# S_ground.net
KiCad netlist of a schematic drawn in Altium Designer
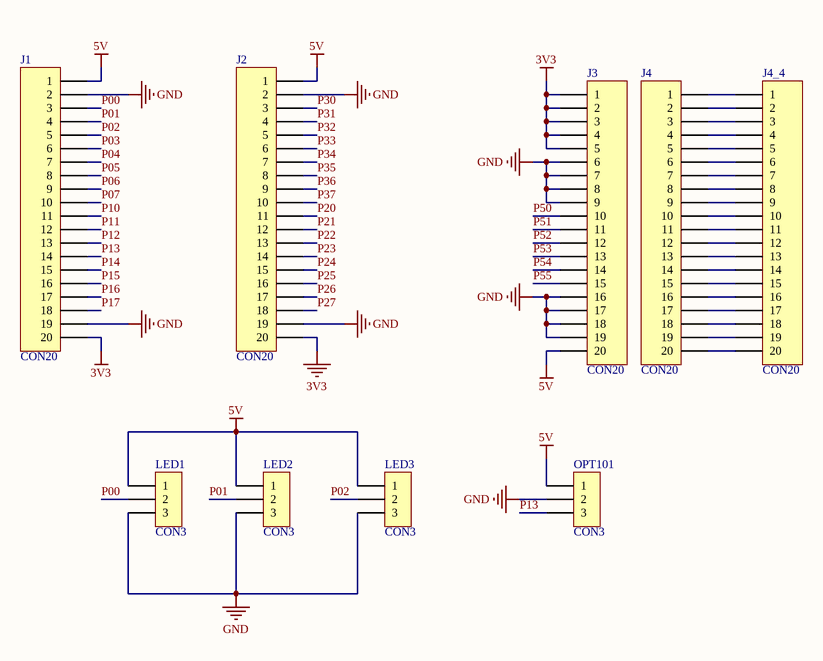
[diagram p0: S_ground.SchDoc]

(export (version "E")
  (design (tool "Eeschema 10.0.6"))
  (components
    (comp (ref "J1")
      (value "CON20")
      (footprint "sip-20")
      (description "Connector")
      (libsource (lib "") (part "CON20_1"))
    )
    (comp (ref "J2")
      (value "CON20")
      (footprint "sip-20")
      (description "Connector")
      (libsource (lib "") (part "CON20_1"))
    )
    (comp (ref "J3")
      (value "CON20")
      (footprint "sip-20")
      (description "Connector")
      (libsource (lib "科协的库") (part "CON20"))
    )
    (comp (ref "J4")
      (value "CON20")
      (footprint "sip-20")
      (description "Connector")
      (libsource (lib "") (part "CON20_1"))
    )
    (comp (ref "J4_4")
      (value "CON20")
      (footprint "sip-20")
      (description "Connector")
      (libsource (lib "科协的库") (part "CON20"))
    )
    (comp (ref "LED1")
      (value "CON3")
      (footprint "SIP-3")
      (description "Connector")
      (libsource (lib "科协的库") (part "CON3"))
    )
    (comp (ref "LED2")
      (value "CON3")
      (footprint "SIP-3")
      (description "Connector")
      (libsource (lib "科协的库") (part "CON3"))
    )
    (comp (ref "LED3")
      (value "CON3")
      (footprint "SIP-3")
      (description "Connector")
      (libsource (lib "科协的库") (part "CON3"))
    )
    (comp (ref "OPT101")
      (value "CON3")
      (footprint "SIP-3")
      (description "Connector")
      (libsource (lib "科协的库") (part "CON3"))
    )
  )
  (nets
    (net (code "1") (name "/P00") (class "Default")
      (node (ref "J1") (pin "3") (pinfunction "3_3") (pintype "passive"))
      (node (ref "LED1") (pin "2") (pinfunction "2_2") (pintype "passive"))
    )
    (net (code "2") (name "/P01") (class "Default")
      (node (ref "J1") (pin "4") (pinfunction "4_4") (pintype "passive"))
      (node (ref "LED2") (pin "2") (pinfunction "2_2") (pintype "passive"))
    )
    (net (code "3") (name "/P02") (class "Default")
      (node (ref "J1") (pin "5") (pinfunction "5_5") (pintype "passive"))
      (node (ref "LED3") (pin "2") (pinfunction "2_2") (pintype "passive"))
    )
    (net (code "4") (name "/P03") (class "Default")
      (node (ref "J1") (pin "6") (pinfunction "6_6") (pintype "passive"))
    )
    (net (code "5") (name "/P04") (class "Default")
      (node (ref "J1") (pin "7") (pinfunction "7_7") (pintype "passive"))
    )
    (net (code "6") (name "/P05") (class "Default")
      (node (ref "J1") (pin "8") (pinfunction "8_8") (pintype "passive"))
    )
    (net (code "7") (name "/P06") (class "Default")
      (node (ref "J1") (pin "9") (pinfunction "9_9") (pintype "passive"))
    )
    (net (code "8") (name "/P07") (class "Default")
      (node (ref "J1") (pin "10") (pinfunction "10_10") (pintype "passive"))
    )
    (net (code "9") (name "/P10") (class "Default")
      (node (ref "J1") (pin "11") (pinfunction "11_11") (pintype "passive"))
    )
    (net (code "10") (name "/P11") (class "Default")
      (node (ref "J1") (pin "12") (pinfunction "12_12") (pintype "passive"))
    )
    (net (code "11") (name "/P12") (class "Default")
      (node (ref "J1") (pin "13") (pinfunction "13_13") (pintype "passive"))
    )
    (net (code "12") (name "/P13") (class "Default")
      (node (ref "J1") (pin "14") (pinfunction "14_14") (pintype "passive"))
      (node (ref "OPT101") (pin "3") (pinfunction "3_3") (pintype "passive"))
    )
    (net (code "13") (name "/P14") (class "Default")
      (node (ref "J1") (pin "15") (pinfunction "15_15") (pintype "passive"))
    )
    (net (code "14") (name "/P15") (class "Default")
      (node (ref "J1") (pin "16") (pinfunction "16_16") (pintype "passive"))
    )
    (net (code "15") (name "/P16") (class "Default")
      (node (ref "J1") (pin "17") (pinfunction "17_17") (pintype "passive"))
    )
    (net (code "16") (name "/P17") (class "Default")
      (node (ref "J1") (pin "18") (pinfunction "18_18") (pintype "passive"))
    )
    (net (code "17") (name "/P20") (class "Default")
      (node (ref "J2") (pin "11") (pinfunction "11_11") (pintype "passive"))
    )
    (net (code "18") (name "/P21") (class "Default")
      (node (ref "J2") (pin "12") (pinfunction "12_12") (pintype "passive"))
    )
    (net (code "19") (name "/P22") (class "Default")
      (node (ref "J2") (pin "13") (pinfunction "13_13") (pintype "passive"))
    )
    (net (code "20") (name "/P23") (class "Default")
      (node (ref "J2") (pin "14") (pinfunction "14_14") (pintype "passive"))
    )
    (net (code "21") (name "/P24") (class "Default")
      (node (ref "J2") (pin "15") (pinfunction "15_15") (pintype "passive"))
    )
    (net (code "22") (name "/P25") (class "Default")
      (node (ref "J2") (pin "16") (pinfunction "16_16") (pintype "passive"))
    )
    (net (code "23") (name "/P26") (class "Default")
      (node (ref "J2") (pin "17") (pinfunction "17_17") (pintype "passive"))
    )
    (net (code "24") (name "/P27") (class "Default")
      (node (ref "J2") (pin "18") (pinfunction "18_18") (pintype "passive"))
    )
    (net (code "25") (name "/P30") (class "Default")
      (node (ref "J2") (pin "3") (pinfunction "3_3") (pintype "passive"))
    )
    (net (code "26") (name "/P31") (class "Default")
      (node (ref "J2") (pin "4") (pinfunction "4_4") (pintype "passive"))
    )
    (net (code "27") (name "/P32") (class "Default")
      (node (ref "J2") (pin "5") (pinfunction "5_5") (pintype "passive"))
    )
    (net (code "28") (name "/P33") (class "Default")
      (node (ref "J2") (pin "6") (pinfunction "6_6") (pintype "passive"))
    )
    (net (code "29") (name "/P34") (class "Default")
      (node (ref "J2") (pin "7") (pinfunction "7_7") (pintype "passive"))
    )
    (net (code "30") (name "/P35") (class "Default")
      (node (ref "J2") (pin "8") (pinfunction "8_8") (pintype "passive"))
    )
    (net (code "31") (name "/P36") (class "Default")
      (node (ref "J2") (pin "9") (pinfunction "9_9") (pintype "passive"))
    )
    (net (code "32") (name "/P37") (class "Default")
      (node (ref "J2") (pin "10") (pinfunction "10_10") (pintype "passive"))
    )
    (net (code "33") (name "/P50") (class "Default")
      (node (ref "J3") (pin "10") (pinfunction "10_10") (pintype "passive"))
    )
    (net (code "34") (name "/P51") (class "Default")
      (node (ref "J3") (pin "11") (pinfunction "11_11") (pintype "passive"))
    )
    (net (code "35") (name "/P52") (class "Default")
      (node (ref "J3") (pin "12") (pinfunction "12_12") (pintype "passive"))
    )
    (net (code "36") (name "/P53") (class "Default")
      (node (ref "J3") (pin "13") (pinfunction "13_13") (pintype "passive"))
    )
    (net (code "37") (name "/P54") (class "Default")
      (node (ref "J3") (pin "14") (pinfunction "14_14") (pintype "passive"))
    )
    (net (code "38") (name "/P55") (class "Default")
      (node (ref "J3") (pin "15") (pinfunction "15_15") (pintype "passive"))
    )
    (net (code "39") (name "3V3") (class "Default")
      (node (ref "J1") (pin "20") (pinfunction "20_20") (pintype "passive"))
      (node (ref "J2") (pin "20") (pinfunction "20_20") (pintype "passive"))
      (node (ref "J3") (pin "1") (pinfunction "1_1") (pintype "passive"))
      (node (ref "J3") (pin "2") (pinfunction "2_2") (pintype "passive"))
      (node (ref "J3") (pin "3") (pinfunction "3_3") (pintype "passive"))
      (node (ref "J3") (pin "4") (pinfunction "4_4") (pintype "passive"))
      (node (ref "J3") (pin "5") (pinfunction "5_5") (pintype "passive"))
    )
    (net (code "40") (name "5V") (class "Default")
      (node (ref "J1") (pin "1") (pinfunction "1_1") (pintype "passive"))
      (node (ref "J2") (pin "1") (pinfunction "1_1") (pintype "passive"))
      (node (ref "J3") (pin "20") (pinfunction "20_20") (pintype "passive"))
      (node (ref "LED1") (pin "1") (pinfunction "1_1") (pintype "passive"))
      (node (ref "LED2") (pin "1") (pinfunction "1_1") (pintype "passive"))
      (node (ref "LED3") (pin "1") (pinfunction "1_1") (pintype "passive"))
      (node (ref "OPT101") (pin "1") (pinfunction "1_1") (pintype "passive"))
    )
    (net (code "41") (name "GND") (class "Default")
      (node (ref "J1") (pin "19") (pinfunction "19_19") (pintype "passive"))
      (node (ref "J1") (pin "2") (pinfunction "2_2") (pintype "passive"))
      (node (ref "J2") (pin "19") (pinfunction "19_19") (pintype "passive"))
      (node (ref "J2") (pin "2") (pinfunction "2_2") (pintype "passive"))
      (node (ref "J3") (pin "16") (pinfunction "16_16") (pintype "passive"))
      (node (ref "J3") (pin "17") (pinfunction "17_17") (pintype "passive"))
      (node (ref "J3") (pin "18") (pinfunction "18_18") (pintype "passive"))
      (node (ref "J3") (pin "19") (pinfunction "19_19") (pintype "passive"))
      (node (ref "J3") (pin "6") (pinfunction "6_6") (pintype "passive"))
      (node (ref "J3") (pin "7") (pinfunction "7_7") (pintype "passive"))
      (node (ref "J3") (pin "8") (pinfunction "8_8") (pintype "passive"))
      (node (ref "J3") (pin "9") (pinfunction "9_9") (pintype "passive"))
      (node (ref "LED1") (pin "3") (pinfunction "3_3") (pintype "passive"))
      (node (ref "LED2") (pin "3") (pinfunction "3_3") (pintype "passive"))
      (node (ref "LED3") (pin "3") (pinfunction "3_3") (pintype "passive"))
      (node (ref "OPT101") (pin "2") (pinfunction "2_2") (pintype "passive"))
    )
    (net (code "42") (name "Net-(J4-Pad1)") (class "Default")
      (node (ref "J4") (pin "1") (pinfunction "1_1") (pintype "passive"))
      (node (ref "J4_4") (pin "1") (pinfunction "1_1") (pintype "passive"))
    )
    (net (code "43") (name "Net-(J4-Pad2)") (class "Default")
      (node (ref "J4") (pin "2") (pinfunction "2_2") (pintype "passive"))
      (node (ref "J4_4") (pin "2") (pinfunction "2_2") (pintype "passive"))
    )
    (net (code "44") (name "Net-(J4-Pad3)") (class "Default")
      (node (ref "J4") (pin "3") (pinfunction "3_3") (pintype "passive"))
      (node (ref "J4_4") (pin "3") (pinfunction "3_3") (pintype "passive"))
    )
    (net (code "45") (name "Net-(J4-Pad4)") (class "Default")
      (node (ref "J4") (pin "4") (pinfunction "4_4") (pintype "passive"))
      (node (ref "J4_4") (pin "4") (pinfunction "4_4") (pintype "passive"))
    )
    (net (code "46") (name "Net-(J4-Pad5)") (class "Default")
      (node (ref "J4") (pin "5") (pinfunction "5_5") (pintype "passive"))
      (node (ref "J4_4") (pin "5") (pinfunction "5_5") (pintype "passive"))
    )
    (net (code "47") (name "Net-(J4-Pad6)") (class "Default")
      (node (ref "J4") (pin "6") (pinfunction "6_6") (pintype "passive"))
      (node (ref "J4_4") (pin "6") (pinfunction "6_6") (pintype "passive"))
    )
    (net (code "48") (name "Net-(J4-Pad7)") (class "Default")
      (node (ref "J4") (pin "7") (pinfunction "7_7") (pintype "passive"))
      (node (ref "J4_4") (pin "7") (pinfunction "7_7") (pintype "passive"))
    )
    (net (code "49") (name "Net-(J4-Pad8)") (class "Default")
      (node (ref "J4") (pin "8") (pinfunction "8_8") (pintype "passive"))
      (node (ref "J4_4") (pin "8") (pinfunction "8_8") (pintype "passive"))
    )
    (net (code "50") (name "Net-(J4-Pad9)") (class "Default")
      (node (ref "J4") (pin "9") (pinfunction "9_9") (pintype "passive"))
      (node (ref "J4_4") (pin "9") (pinfunction "9_9") (pintype "passive"))
    )
    (net (code "51") (name "Net-(J4-Pad10)") (class "Default")
      (node (ref "J4") (pin "10") (pinfunction "10_10") (pintype "passive"))
      (node (ref "J4_4") (pin "10") (pinfunction "10_10") (pintype "passive"))
    )
    (net (code "52") (name "Net-(J4-Pad11)") (class "Default")
      (node (ref "J4") (pin "11") (pinfunction "11_11") (pintype "passive"))
      (node (ref "J4_4") (pin "11") (pinfunction "11_11") (pintype "passive"))
    )
    (net (code "53") (name "Net-(J4-Pad12)") (class "Default")
      (node (ref "J4") (pin "12") (pinfunction "12_12") (pintype "passive"))
      (node (ref "J4_4") (pin "12") (pinfunction "12_12") (pintype "passive"))
    )
    (net (code "54") (name "Net-(J4-Pad13)") (class "Default")
      (node (ref "J4") (pin "13") (pinfunction "13_13") (pintype "passive"))
      (node (ref "J4_4") (pin "13") (pinfunction "13_13") (pintype "passive"))
    )
    (net (code "55") (name "Net-(J4-Pad14)") (class "Default")
      (node (ref "J4") (pin "14") (pinfunction "14_14") (pintype "passive"))
      (node (ref "J4_4") (pin "14") (pinfunction "14_14") (pintype "passive"))
    )
    (net (code "56") (name "Net-(J4-Pad15)") (class "Default")
      (node (ref "J4") (pin "15") (pinfunction "15_15") (pintype "passive"))
      (node (ref "J4_4") (pin "15") (pinfunction "15_15") (pintype "passive"))
    )
    (net (code "57") (name "Net-(J4-Pad16)") (class "Default")
      (node (ref "J4") (pin "16") (pinfunction "16_16") (pintype "passive"))
      (node (ref "J4_4") (pin "16") (pinfunction "16_16") (pintype "passive"))
    )
    (net (code "58") (name "Net-(J4-Pad17)") (class "Default")
      (node (ref "J4") (pin "17") (pinfunction "17_17") (pintype "passive"))
      (node (ref "J4_4") (pin "17") (pinfunction "17_17") (pintype "passive"))
    )
    (net (code "59") (name "Net-(J4-Pad18)") (class "Default")
      (node (ref "J4") (pin "18") (pinfunction "18_18") (pintype "passive"))
      (node (ref "J4_4") (pin "18") (pinfunction "18_18") (pintype "passive"))
    )
    (net (code "60") (name "Net-(J4-Pad19)") (class "Default")
      (node (ref "J4") (pin "19") (pinfunction "19_19") (pintype "passive"))
      (node (ref "J4_4") (pin "19") (pinfunction "19_19") (pintype "passive"))
    )
    (net (code "61") (name "Net-(J4-Pad20)") (class "Default")
      (node (ref "J4") (pin "20") (pinfunction "20_20") (pintype "passive"))
      (node (ref "J4_4") (pin "20") (pinfunction "20_20") (pintype "passive"))
    )
  )
)
